# Sheet1.net
KiCad netlist of a schematic drawn in Altium Designer
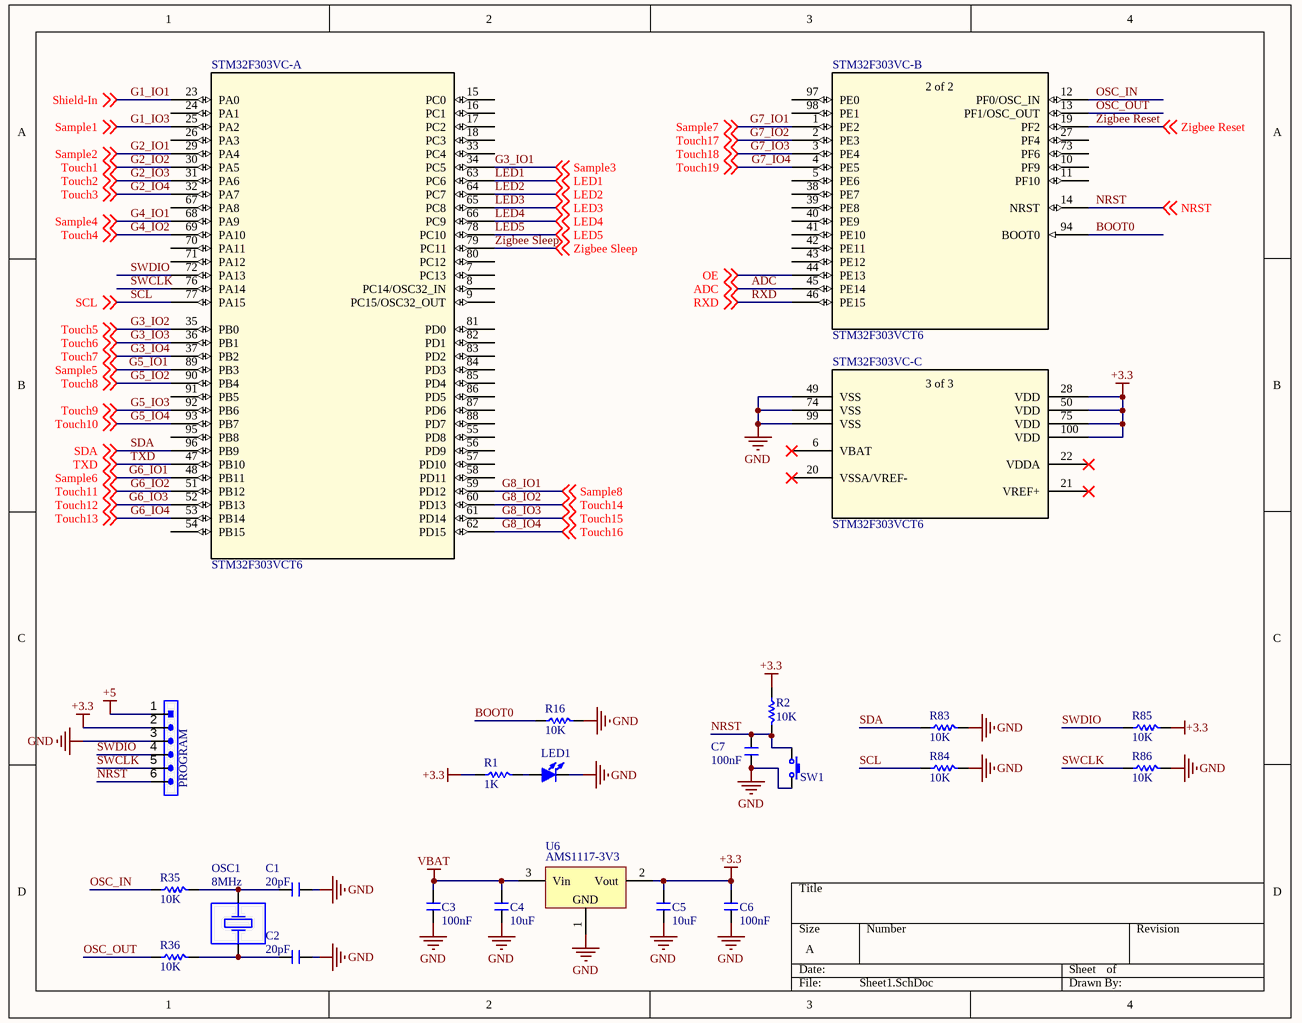
[diagram p0: Sheet1.SchDoc]

(export (version "E")
  (design (tool "Eeschema 10.0.6"))
  (components
    (comp (ref "C1")
      (value "20pF")
      (footprint "C 0805")
      (description "Non-polar patch capacitor")
      (fields (field (name "版权归属") "源创客"))
      (libsource (lib "Passive (Resistor-Capacitor-Inductor-Veristor-Ferrite)") (part "C"))
    )
    (comp (ref "C2")
      (value "20pF")
      (footprint "C 0805")
      (description "Non-polar patch capacitor")
      (fields (field (name "版权归属") "源创客"))
      (libsource (lib "Passive (Resistor-Capacitor-Inductor-Veristor-Ferrite)") (part "C"))
    )
    (comp (ref "C3")
      (value "100nF")
      (footprint "C 0805")
      (description "Non-polar patch capacitor")
      (fields (field (name "版权归属") "源创客"))
      (libsource (lib "Passive (Resistor-Capacitor-Inductor-Veristor-Ferrite)") (part "C"))
    )
    (comp (ref "C4")
      (value "10uF")
      (footprint "C 0805")
      (description "Non-polar patch capacitor")
      (fields (field (name "版权归属") "源创客"))
      (libsource (lib "Passive (Resistor-Capacitor-Inductor-Veristor-Ferrite)") (part "C"))
    )
    (comp (ref "C5")
      (value "10uF")
      (footprint "C 0805")
      (description "Non-polar patch capacitor")
      (fields (field (name "版权归属") "源创客"))
      (libsource (lib "Passive (Resistor-Capacitor-Inductor-Veristor-Ferrite)") (part "C"))
    )
    (comp (ref "C6")
      (value "100nF")
      (footprint "C 0805")
      (description "Non-polar patch capacitor")
      (fields (field (name "版权归属") "源创客"))
      (libsource (lib "Passive (Resistor-Capacitor-Inductor-Veristor-Ferrite)") (part "C"))
    )
    (comp (ref "C7")
      (value "100nF")
      (footprint "C 0805")
      (description "Non-polar patch capacitor")
      (fields (field (name "版权归属") "源创客"))
      (libsource (lib "Passive (Resistor-Capacitor-Inductor-Veristor-Ferrite)") (part "C"))
    )
    (comp (ref "LED1")
      (value "LED-SMD")
      (footprint "LED 0805R")
      (description "Patch LED")
      (fields (field (name "版权归属") "源创客"))
      (libsource (lib "LED") (part "LED-SMD"))
    )
    (comp (ref "OSC1")
      (value "8MHz")
      (footprint "XTAL-HC49S-THD")
      (description "2-Pin crystal")
      (fields (field (name "版权归属") "源创客"))
      (libsource (lib "Crystal Oscillator") (part "XTAL-2"))
    )
    (comp (ref "PROGRAM")
      (value "HDR-1X6")
      (footprint "HDR-1X6")
      (description "6P Connector")
      (fields (field (name "版权归属") "源创客"))
      (libsource (lib "Connectors") (part "Header 6"))
    )
    (comp (ref "R1")
      (value "1K")
      (footprint "R 0805")
      (description "Chip resistor")
      (fields (field (name "版权归属") "源创客"))
      (libsource (lib "Passive (Resistor-Capacitor-Inductor-Veristor-Ferrite)") (part "R"))
    )
    (comp (ref "R2")
      (value "10K")
      (footprint "R 0805")
      (description "Chip resistor")
      (fields (field (name "版权归属") "源创客"))
      (libsource (lib "Passive (Resistor-Capacitor-Inductor-Veristor-Ferrite)") (part "R"))
    )
    (comp (ref "R16")
      (value "10K")
      (footprint "R 0805")
      (description "Chip resistor")
      (fields (field (name "版权归属") "源创客"))
      (libsource (lib "Passive (Resistor-Capacitor-Inductor-Veristor-Ferrite)") (part "R"))
    )
    (comp (ref "R35")
      (value "10K")
      (footprint "R 0805")
      (description "Chip resistor")
      (fields (field (name "版权归属") "源创客"))
      (libsource (lib "Passive (Resistor-Capacitor-Inductor-Veristor-Ferrite)") (part "R"))
    )
    (comp (ref "R36")
      (value "10K")
      (footprint "R 0805")
      (description "Chip resistor")
      (fields (field (name "版权归属") "源创客"))
      (libsource (lib "Passive (Resistor-Capacitor-Inductor-Veristor-Ferrite)") (part "R"))
    )
    (comp (ref "R83")
      (value "10K")
      (footprint "R 0805")
      (description "Chip resistor")
      (fields (field (name "版权归属") "源创客"))
      (libsource (lib "Passive (Resistor-Capacitor-Inductor-Veristor-Ferrite)") (part "R"))
    )
    (comp (ref "R84")
      (value "10K")
      (footprint "R 0805")
      (description "Chip resistor")
      (fields (field (name "版权归属") "源创客"))
      (libsource (lib "Passive (Resistor-Capacitor-Inductor-Veristor-Ferrite)") (part "R"))
    )
    (comp (ref "R85")
      (value "10K")
      (footprint "R 0805")
      (description "Chip resistor")
      (fields (field (name "版权归属") "源创客"))
      (libsource (lib "Passive (Resistor-Capacitor-Inductor-Veristor-Ferrite)") (part "R"))
    )
    (comp (ref "R86")
      (value "10K")
      (footprint "R 0805")
      (description "Chip resistor")
      (fields (field (name "版权归属") "源创客"))
      (libsource (lib "Passive (Resistor-Capacitor-Inductor-Veristor-Ferrite)") (part "R"))
    )
    (comp (ref "STM32F303VC-")
      (value "STM32F303VCT6")
      (footprint "LQFP100_STM")
      (description "No Description Available")
      (fields (field (name "COPYRIGHT") "Copyright (C) 2018 Accelerated Designs. All rights reserved"))
      (libsource (lib "STM32F303VCT6") (part "STM32F303VCT6"))
    )
    (comp (ref "SW1")
      (value "3x6x5")
      (footprint "TSW SMD-3*6*2.5")
      (description "3x6 tact switch")
      (fields (field (name "版权归属") "源创客"))
      (libsource (lib "Button") (part "TSW 3x6"))
    )
    (comp (ref "U6")
      (value "AMS1117-3V3")
      (footprint "SOT223_L")
      (description "Three-terminal regulator chip")
      (fields (field (name "版权归属") "源创客"))
      (libsource (lib "Integrated Circuit") (part "AMS1117"))
    )
  )
  (nets
    (net (code "1") (name "+3.3") (class "Default")
      (node (ref "C5") (pin "2") (pinfunction "2_2") (pintype "passive"))
      (node (ref "C6") (pin "2") (pinfunction "2_2") (pintype "passive"))
      (node (ref "PROGRAM") (pin "2") (pintype "passive"))
      (node (ref "R1") (pin "1") (pinfunction "1_1") (pintype "passive"))
      (node (ref "R2") (pin "1") (pinfunction "1_1") (pintype "passive"))
      (node (ref "R85") (pin "2") (pinfunction "2_2") (pintype "passive"))
      (node (ref "STM32F303VC-") (pin "100") (pinfunction "VDD_100") (pintype "power_in"))
      (node (ref "STM32F303VC-") (pin "28") (pinfunction "VDD_28") (pintype "power_in"))
      (node (ref "STM32F303VC-") (pin "50") (pinfunction "VDD_50") (pintype "power_in"))
      (node (ref "STM32F303VC-") (pin "75") (pinfunction "VDD_75") (pintype "power_in"))
      (node (ref "U6") (pin "2") (pinfunction "Vout_2") (pintype "passive"))
    )
    (net (code "2") (name "+5") (class "Default") (node (ref "PROGRAM") (pin "1") (pintype "passive")))
    (net (code "3") (name "/BOOT0") (class "Default")
      (node (ref "R16") (pin "1") (pinfunction "1_1") (pintype "passive"))
      (node (ref "STM32F303VC-") (pin "94") (pinfunction "BOOT0_94") (pintype "input"))
    )
    (net (code "4") (name "/OSC_IN") (class "Default")
      (node (ref "R35") (pin "1") (pinfunction "1_1") (pintype "passive"))
      (node (ref "STM32F303VC-") (pin "12") (pinfunction "PF0/OSC_IN_12") (pintype "bidirectional"))
    )
    (net (code "5") (name "/OSC_OUT") (class "Default")
      (node (ref "R36") (pin "1") (pinfunction "1_1") (pintype "passive"))
      (node (ref "STM32F303VC-") (pin "13") (pinfunction "PF1/OSC_OUT_13") (pintype "bidirectional"))
    )
    (net (code "6") (name "/SWCLK") (class "Default")
      (node (ref "PROGRAM") (pin "5") (pintype "passive"))
      (node (ref "R86") (pin "1") (pinfunction "1_1") (pintype "passive"))
      (node (ref "STM32F303VC-") (pin "76") (pinfunction "PA14_76") (pintype "bidirectional"))
    )
    (net (code "7") (name "/SWDIO") (class "Default")
      (node (ref "PROGRAM") (pin "4") (pintype "passive"))
      (node (ref "R85") (pin "1") (pinfunction "1_1") (pintype "passive"))
      (node (ref "STM32F303VC-") (pin "72") (pinfunction "PA13_72") (pintype "bidirectional"))
    )
    (net (code "8") (name "ADC") (class "Default")
      (node (ref "STM32F303VC-") (pin "45") (pinfunction "PE14_45") (pintype "bidirectional"))
    )
    (net (code "9") (name "GND") (class "Default")
      (node (ref "C1") (pin "1") (pinfunction "1_1") (pintype "passive"))
      (node (ref "C2") (pin "1") (pinfunction "1_1") (pintype "passive"))
      (node (ref "C3") (pin "1") (pinfunction "1_1") (pintype "passive"))
      (node (ref "C4") (pin "1") (pinfunction "1_1") (pintype "passive"))
      (node (ref "C5") (pin "1") (pinfunction "1_1") (pintype "passive"))
      (node (ref "C6") (pin "1") (pinfunction "1_1") (pintype "passive"))
      (node (ref "C7") (pin "1") (pinfunction "1_1") (pintype "passive"))
      (node (ref "LED1") (pin "2") (pinfunction "K_2") (pintype "passive"))
      (node (ref "PROGRAM") (pin "3") (pintype "passive"))
      (node (ref "R16") (pin "2") (pinfunction "2_2") (pintype "passive"))
      (node (ref "R83") (pin "2") (pinfunction "2_2") (pintype "passive"))
      (node (ref "R84") (pin "2") (pinfunction "2_2") (pintype "passive"))
      (node (ref "R86") (pin "2") (pinfunction "2_2") (pintype "passive"))
      (node (ref "STM32F303VC-") (pin "49") (pinfunction "VSS_49") (pintype "power_in"))
      (node (ref "STM32F303VC-") (pin "74") (pinfunction "VSS_74") (pintype "power_in"))
      (node (ref "STM32F303VC-") (pin "99") (pinfunction "VSS_99") (pintype "power_in"))
      (node (ref "SW1") (pin "2") (pinfunction "2_2") (pintype "passive"))
      (node (ref "U6") (pin "1") (pinfunction "GND_1") (pintype "passive"))
    )
    (net (code "10") (name "LED1") (class "Default")
      (node (ref "STM32F303VC-") (pin "63") (pinfunction "PC6_63") (pintype "bidirectional"))
    )
    (net (code "11") (name "LED2") (class "Default")
      (node (ref "STM32F303VC-") (pin "64") (pinfunction "PC7_64") (pintype "bidirectional"))
    )
    (net (code "12") (name "LED3") (class "Default")
      (node (ref "STM32F303VC-") (pin "65") (pinfunction "PC8_65") (pintype "bidirectional"))
    )
    (net (code "13") (name "LED4") (class "Default")
      (node (ref "STM32F303VC-") (pin "66") (pinfunction "PC9_66") (pintype "bidirectional"))
    )
    (net (code "14") (name "LED5") (class "Default")
      (node (ref "STM32F303VC-") (pin "78") (pinfunction "PC10_78") (pintype "bidirectional"))
    )
    (net (code "15") (name "NRST") (class "Default")
      (node (ref "C7") (pin "2") (pinfunction "2_2") (pintype "passive"))
      (node (ref "PROGRAM") (pin "6") (pintype "passive"))
      (node (ref "R2") (pin "2") (pinfunction "2_2") (pintype "passive"))
      (node (ref "STM32F303VC-") (pin "14") (pinfunction "NRST_14") (pintype "bidirectional"))
      (node (ref "SW1") (pin "1") (pinfunction "1_1") (pintype "passive"))
    )
    (net (code "16") (name "Net-(C2-Pad2)") (class "Default")
      (node (ref "C2") (pin "2") (pinfunction "2_2") (pintype "passive"))
      (node (ref "OSC1") (pin "1") (pinfunction "1_1") (pintype "passive"))
      (node (ref "R36") (pin "2") (pinfunction "2_2") (pintype "passive"))
    )
    (net (code "17") (name "Net-(LED1-A)") (class "Default")
      (node (ref "LED1") (pin "1") (pinfunction "A_1") (pintype "passive"))
      (node (ref "R1") (pin "2") (pinfunction "2_2") (pintype "passive"))
    )
    (net (code "18") (name "Net-(OSC1-3)") (class "Default")
      (node (ref "C1") (pin "2") (pinfunction "2_2") (pintype "passive"))
      (node (ref "OSC1") (pin "2") (pinfunction "3_2") (pintype "passive"))
      (node (ref "R35") (pin "2") (pinfunction "2_2") (pintype "passive"))
    )
    (net (code "19") (name "OE") (class "Default")
      (node (ref "STM32F303VC-") (pin "44") (pinfunction "PE13_44") (pintype "bidirectional"))
    )
    (net (code "20") (name "RXD") (class "Default")
      (node (ref "STM32F303VC-") (pin "46") (pinfunction "PE15_46") (pintype "bidirectional"))
    )
    (net (code "21") (name "SCL") (class "Default")
      (node (ref "R84") (pin "1") (pinfunction "1_1") (pintype "passive"))
      (node (ref "STM32F303VC-") (pin "77") (pinfunction "PA15_77") (pintype "bidirectional"))
    )
    (net (code "22") (name "SDA") (class "Default")
      (node (ref "R83") (pin "1") (pinfunction "1_1") (pintype "passive"))
      (node (ref "STM32F303VC-") (pin "96") (pinfunction "PB9_96") (pintype "bidirectional"))
    )
    (net (code "23") (name "Sample1") (class "Default")
      (node (ref "STM32F303VC-") (pin "25") (pinfunction "PA2_25") (pintype "bidirectional"))
    )
    (net (code "24") (name "Sample2") (class "Default")
      (node (ref "STM32F303VC-") (pin "29") (pinfunction "PA4_29") (pintype "bidirectional"))
    )
    (net (code "25") (name "Sample3") (class "Default")
      (node (ref "STM32F303VC-") (pin "34") (pinfunction "PC5_34") (pintype "bidirectional"))
    )
    (net (code "26") (name "Sample4") (class "Default")
      (node (ref "STM32F303VC-") (pin "68") (pinfunction "PA9_68") (pintype "bidirectional"))
    )
    (net (code "27") (name "Sample5") (class "Default")
      (node (ref "STM32F303VC-") (pin "89") (pinfunction "PB3_89") (pintype "bidirectional"))
    )
    (net (code "28") (name "Sample6") (class "Default")
      (node (ref "STM32F303VC-") (pin "48") (pinfunction "PB11_48") (pintype "bidirectional"))
    )
    (net (code "29") (name "Sample7") (class "Default")
      (node (ref "STM32F303VC-") (pin "1") (pinfunction "PE2_1") (pintype "bidirectional"))
    )
    (net (code "30") (name "Sample8") (class "Default")
      (node (ref "STM32F303VC-") (pin "59") (pinfunction "PD12_59") (pintype "bidirectional"))
    )
    (net (code "31") (name "Shield-In") (class "Default")
      (node (ref "STM32F303VC-") (pin "23") (pinfunction "PA0_23") (pintype "bidirectional"))
    )
    (net (code "32") (name "TXD") (class "Default")
      (node (ref "STM32F303VC-") (pin "47") (pinfunction "PB10_47") (pintype "bidirectional"))
    )
    (net (code "33") (name "Touch1") (class "Default")
      (node (ref "STM32F303VC-") (pin "30") (pinfunction "PA5_30") (pintype "bidirectional"))
    )
    (net (code "34") (name "Touch2") (class "Default")
      (node (ref "STM32F303VC-") (pin "31") (pinfunction "PA6_31") (pintype "bidirectional"))
    )
    (net (code "35") (name "Touch3") (class "Default")
      (node (ref "STM32F303VC-") (pin "32") (pinfunction "PA7_32") (pintype "bidirectional"))
    )
    (net (code "36") (name "Touch4") (class "Default")
      (node (ref "STM32F303VC-") (pin "69") (pinfunction "PA10_69") (pintype "bidirectional"))
    )
    (net (code "37") (name "Touch5") (class "Default")
      (node (ref "STM32F303VC-") (pin "35") (pinfunction "PB0_35") (pintype "bidirectional"))
    )
    (net (code "38") (name "Touch6") (class "Default")
      (node (ref "STM32F303VC-") (pin "36") (pinfunction "PB1_36") (pintype "bidirectional"))
    )
    (net (code "39") (name "Touch7") (class "Default")
      (node (ref "STM32F303VC-") (pin "37") (pinfunction "PB2_37") (pintype "bidirectional"))
    )
    (net (code "40") (name "Touch8") (class "Default")
      (node (ref "STM32F303VC-") (pin "90") (pinfunction "PB4_90") (pintype "bidirectional"))
    )
    (net (code "41") (name "Touch9") (class "Default")
      (node (ref "STM32F303VC-") (pin "92") (pinfunction "PB6_92") (pintype "bidirectional"))
    )
    (net (code "42") (name "Touch10") (class "Default")
      (node (ref "STM32F303VC-") (pin "93") (pinfunction "PB7_93") (pintype "bidirectional"))
    )
    (net (code "43") (name "Touch11") (class "Default")
      (node (ref "STM32F303VC-") (pin "51") (pinfunction "PB12_51") (pintype "bidirectional"))
    )
    (net (code "44") (name "Touch12") (class "Default")
      (node (ref "STM32F303VC-") (pin "52") (pinfunction "PB13_52") (pintype "bidirectional"))
    )
    (net (code "45") (name "Touch13") (class "Default")
      (node (ref "STM32F303VC-") (pin "53") (pinfunction "PB14_53") (pintype "bidirectional"))
    )
    (net (code "46") (name "Touch14") (class "Default")
      (node (ref "STM32F303VC-") (pin "60") (pinfunction "PD13_60") (pintype "bidirectional"))
    )
    (net (code "47") (name "Touch15") (class "Default")
      (node (ref "STM32F303VC-") (pin "61") (pinfunction "PD14_61") (pintype "bidirectional"))
    )
    (net (code "48") (name "Touch16") (class "Default")
      (node (ref "STM32F303VC-") (pin "62") (pinfunction "PD15_62") (pintype "bidirectional"))
    )
    (net (code "49") (name "Touch17") (class "Default")
      (node (ref "STM32F303VC-") (pin "2") (pinfunction "PE3_2") (pintype "bidirectional"))
    )
    (net (code "50") (name "Touch18") (class "Default")
      (node (ref "STM32F303VC-") (pin "3") (pinfunction "PE4_3") (pintype "bidirectional"))
    )
    (net (code "51") (name "Touch19") (class "Default")
      (node (ref "STM32F303VC-") (pin "4") (pinfunction "PE5_4") (pintype "bidirectional"))
    )
    (net (code "52") (name "VBAT") (class "Default")
      (node (ref "C3") (pin "2") (pinfunction "2_2") (pintype "passive"))
      (node (ref "C4") (pin "2") (pinfunction "2_2") (pintype "passive"))
      (node (ref "U6") (pin "3") (pinfunction "Vin_3") (pintype "passive"))
    )
    (net (code "53") (name "Zigbee Reset") (class "Default")
      (node (ref "STM32F303VC-") (pin "19") (pinfunction "PF2_19") (pintype "bidirectional"))
    )
    (net (code "54") (name "Zigbee Sleep") (class "Default")
      (node (ref "STM32F303VC-") (pin "79") (pinfunction "PC11_79") (pintype "bidirectional"))
    )
    (net (code "55") (name "unconnected-(STM32F303VC-A-PA1-Pad24)") (class "Default")
      (node (ref "STM32F303VC-") (pin "24") (pinfunction "PA1_24") (pintype "bidirectional"))
    )
    (net (code "56") (name "unconnected-(STM32F303VC-A-PA3-Pad26)") (class "Default")
      (node (ref "STM32F303VC-") (pin "26") (pinfunction "PA3_26") (pintype "bidirectional"))
    )
    (net (code "57") (name "unconnected-(STM32F303VC-A-PA8-Pad67)") (class "Default")
      (node (ref "STM32F303VC-") (pin "67") (pinfunction "PA8_67") (pintype "bidirectional"))
    )
    (net (code "58") (name "unconnected-(STM32F303VC-A-PA11-Pad70)") (class "Default")
      (node (ref "STM32F303VC-") (pin "70") (pinfunction "PA11_70") (pintype "bidirectional"))
    )
    (net (code "59") (name "unconnected-(STM32F303VC-A-PA12-Pad71)") (class "Default")
      (node (ref "STM32F303VC-") (pin "71") (pinfunction "PA12_71") (pintype "bidirectional"))
    )
    (net (code "60") (name "unconnected-(STM32F303VC-A-PB5-Pad91)") (class "Default")
      (node (ref "STM32F303VC-") (pin "91") (pinfunction "PB5_91") (pintype "bidirectional"))
    )
    (net (code "61") (name "unconnected-(STM32F303VC-A-PB8-Pad95)") (class "Default")
      (node (ref "STM32F303VC-") (pin "95") (pinfunction "PB8_95") (pintype "bidirectional"))
    )
    (net (code "62") (name "unconnected-(STM32F303VC-A-PB15-Pad54)") (class "Default")
      (node (ref "STM32F303VC-") (pin "54") (pinfunction "PB15_54") (pintype "bidirectional"))
    )
    (net (code "63") (name "unconnected-(STM32F303VC-A-PC0-Pad15)") (class "Default")
      (node (ref "STM32F303VC-") (pin "15") (pinfunction "PC0_15") (pintype "bidirectional"))
    )
    (net (code "64") (name "unconnected-(STM32F303VC-A-PC1-Pad16)") (class "Default")
      (node (ref "STM32F303VC-") (pin "16") (pinfunction "PC1_16") (pintype "bidirectional"))
    )
    (net (code "65") (name "unconnected-(STM32F303VC-A-PC2-Pad17)") (class "Default")
      (node (ref "STM32F303VC-") (pin "17") (pinfunction "PC2_17") (pintype "bidirectional"))
    )
    (net (code "66") (name "unconnected-(STM32F303VC-A-PC3-Pad18)") (class "Default")
      (node (ref "STM32F303VC-") (pin "18") (pinfunction "PC3_18") (pintype "bidirectional"))
    )
    (net (code "67") (name "unconnected-(STM32F303VC-A-PC4-Pad33)") (class "Default")
      (node (ref "STM32F303VC-") (pin "33") (pinfunction "PC4_33") (pintype "bidirectional"))
    )
    (net (code "68") (name "unconnected-(STM32F303VC-A-PC12-Pad80)") (class "Default")
      (node (ref "STM32F303VC-") (pin "80") (pinfunction "PC12_80") (pintype "bidirectional"))
    )
    (net (code "69") (name "unconnected-(STM32F303VC-A-PC13-Pad7)") (class "Default")
      (node (ref "STM32F303VC-") (pin "7") (pinfunction "PC13_7") (pintype "bidirectional"))
    )
    (net (code "70") (name "unconnected-(STM32F303VC-A-PC14{slash}OSC32_IN-Pad8)") (class "Default")
      (node (ref "STM32F303VC-") (pin "8") (pinfunction "PC14/OSC32_IN_8") (pintype "bidirectional"))
    )
    (net (code "71") (name "unconnected-(STM32F303VC-A-PC15{slash}OSC32_OUT-Pad9)") (class "Default")
      (node (ref "STM32F303VC-") (pin "9") (pinfunction "PC15/OSC32_OUT_9") (pintype "bidirectional"))
    )
    (net (code "72") (name "unconnected-(STM32F303VC-A-PD0-Pad81)") (class "Default")
      (node (ref "STM32F303VC-") (pin "81") (pinfunction "PD0_81") (pintype "bidirectional"))
    )
    (net (code "73") (name "unconnected-(STM32F303VC-A-PD1-Pad82)") (class "Default")
      (node (ref "STM32F303VC-") (pin "82") (pinfunction "PD1_82") (pintype "bidirectional"))
    )
    (net (code "74") (name "unconnected-(STM32F303VC-A-PD2-Pad83)") (class "Default")
      (node (ref "STM32F303VC-") (pin "83") (pinfunction "PD2_83") (pintype "bidirectional"))
    )
    (net (code "75") (name "unconnected-(STM32F303VC-A-PD3-Pad84)") (class "Default")
      (node (ref "STM32F303VC-") (pin "84") (pinfunction "PD3_84") (pintype "bidirectional"))
    )
    (net (code "76") (name "unconnected-(STM32F303VC-A-PD4-Pad85)") (class "Default")
      (node (ref "STM32F303VC-") (pin "85") (pinfunction "PD4_85") (pintype "bidirectional"))
    )
    (net (code "77") (name "unconnected-(STM32F303VC-A-PD5-Pad86)") (class "Default")
      (node (ref "STM32F303VC-") (pin "86") (pinfunction "PD5_86") (pintype "bidirectional"))
    )
    (net (code "78") (name "unconnected-(STM32F303VC-A-PD6-Pad87)") (class "Default")
      (node (ref "STM32F303VC-") (pin "87") (pinfunction "PD6_87") (pintype "bidirectional"))
    )
    (net (code "79") (name "unconnected-(STM32F303VC-A-PD7-Pad88)") (class "Default")
      (node (ref "STM32F303VC-") (pin "88") (pinfunction "PD7_88") (pintype "bidirectional"))
    )
    (net (code "80") (name "unconnected-(STM32F303VC-A-PD8-Pad55)") (class "Default")
      (node (ref "STM32F303VC-") (pin "55") (pinfunction "PD8_55") (pintype "bidirectional"))
    )
    (net (code "81") (name "unconnected-(STM32F303VC-A-PD9-Pad56)") (class "Default")
      (node (ref "STM32F303VC-") (pin "56") (pinfunction "PD9_56") (pintype "bidirectional"))
    )
    (net (code "82") (name "unconnected-(STM32F303VC-A-PD10-Pad57)") (class "Default")
      (node (ref "STM32F303VC-") (pin "57") (pinfunction "PD10_57") (pintype "bidirectional"))
    )
    (net (code "83") (name "unconnected-(STM32F303VC-A-PD11-Pad58)") (class "Default")
      (node (ref "STM32F303VC-") (pin "58") (pinfunction "PD11_58") (pintype "bidirectional"))
    )
    (net (code "84") (name "unconnected-(STM32F303VC-B-PE0-Pad97)") (class "Default")
      (node (ref "STM32F303VC-") (pin "97") (pinfunction "PE0_97") (pintype "bidirectional"))
    )
    (net (code "85") (name "unconnected-(STM32F303VC-B-PE1-Pad98)") (class "Default")
      (node (ref "STM32F303VC-") (pin "98") (pinfunction "PE1_98") (pintype "bidirectional"))
    )
    (net (code "86") (name "unconnected-(STM32F303VC-B-PE6-Pad5)") (class "Default")
      (node (ref "STM32F303VC-") (pin "5") (pinfunction "PE6_5") (pintype "bidirectional"))
    )
    (net (code "87") (name "unconnected-(STM32F303VC-B-PE7-Pad38)") (class "Default")
      (node (ref "STM32F303VC-") (pin "38") (pinfunction "PE7_38") (pintype "bidirectional"))
    )
    (net (code "88") (name "unconnected-(STM32F303VC-B-PE8-Pad39)") (class "Default")
      (node (ref "STM32F303VC-") (pin "39") (pinfunction "PE8_39") (pintype "bidirectional"))
    )
    (net (code "89") (name "unconnected-(STM32F303VC-B-PE9-Pad40)") (class "Default")
      (node (ref "STM32F303VC-") (pin "40") (pinfunction "PE9_40") (pintype "bidirectional"))
    )
    (net (code "90") (name "unconnected-(STM32F303VC-B-PE10-Pad41)") (class "Default")
      (node (ref "STM32F303VC-") (pin "41") (pinfunction "PE10_41") (pintype "bidirectional"))
    )
    (net (code "91") (name "unconnected-(STM32F303VC-B-PE11-Pad42)") (class "Default")
      (node (ref "STM32F303VC-") (pin "42") (pinfunction "PE11_42") (pintype "bidirectional"))
    )
    (net (code "92") (name "unconnected-(STM32F303VC-B-PE12-Pad43)") (class "Default")
      (node (ref "STM32F303VC-") (pin "43") (pinfunction "PE12_43") (pintype "bidirectional"))
    )
    (net (code "93") (name "unconnected-(STM32F303VC-B-PF4-Pad27)") (class "Default")
      (node (ref "STM32F303VC-") (pin "27") (pinfunction "PF4_27") (pintype "bidirectional"))
    )
    (net (code "94") (name "unconnected-(STM32F303VC-B-PF6-Pad73)") (class "Default")
      (node (ref "STM32F303VC-") (pin "73") (pinfunction "PF6_73") (pintype "bidirectional"))
    )
    (net (code "95") (name "unconnected-(STM32F303VC-B-PF9-Pad10)") (class "Default")
      (node (ref "STM32F303VC-") (pin "10") (pinfunction "PF9_10") (pintype "bidirectional"))
    )
    (net (code "96") (name "unconnected-(STM32F303VC-B-PF10-Pad11)") (class "Default")
      (node (ref "STM32F303VC-") (pin "11") (pinfunction "PF10_11") (pintype "bidirectional"))
    )
    (net (code "97") (name "unconnected-(STM32F303VC-C-VBAT-Pad6)") (class "Default")
      (node (ref "STM32F303VC-") (pin "6") (pinfunction "VBAT_6") (pintype "power_in+no_connect"))
    )
    (net (code "98") (name "unconnected-(STM32F303VC-C-VDDA-Pad22)") (class "Default")
      (node (ref "STM32F303VC-") (pin "22") (pinfunction "VDDA_22") (pintype "power_in+no_connect"))
    )
    (net (code "99") (name "unconnected-(STM32F303VC-C-VREF+-Pad21)") (class "Default")
      (node (ref "STM32F303VC-") (pin "21") (pinfunction "VREF+_21") (pintype "power_in+no_connect"))
    )
    (net (code "100") (name "unconnected-(STM32F303VC-C-VSSA{slash}VREF--Pad20)") (class "Default")
      (node (ref "STM32F303VC-") (pin "20") (pinfunction "VSSA/VREF-_20") (pintype "power_in+no_connect"))
    )
  )
)
